# CAN-Transceiver.net
KiCad netlist of a schematic drawn in Altium Designer
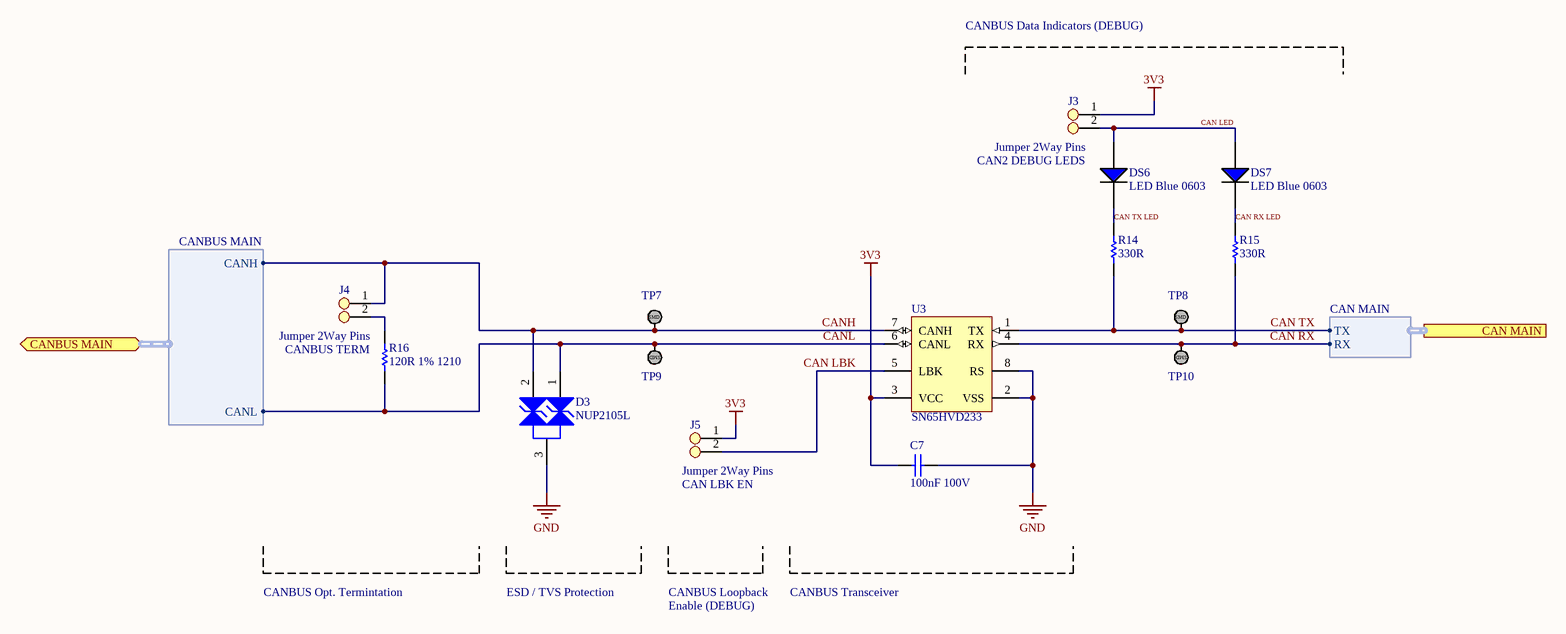
[diagram p0: CAN-Transceiver.SchDoc]

(export (version "E")
  (design (tool "Eeschema 10.0.6"))
  (components
    (comp (ref "C7")
      (value "100nF 100V")
      (footprint "Cap_Ceramic_0603")
      (description "Capacitor, Ceramic, SMD, 100nF, 100V, 5%, X7R, 0603")
      (libsource (lib "StandardCapacitors") (part "100nF 100V 5% X7R 0603"))
    )
    (comp (ref "D3")
      (value "NUP2105L")
      (footprint "NUP2105L")
      (libsource (lib "QUTMS_CANLibrary") (part "NUP2105L"))
    )
    (comp (ref "DS6")
      (value "LED Blue 0603")
      (footprint "LED BLUE 0603")
      (libsource (lib "QUTMS_LEDLibrary") (part "LED BLUE 0603"))
    )
    (comp (ref "DS7")
      (value "LED Blue 0603")
      (footprint "LED BLUE 0603")
      (libsource (lib "QUTMS_LEDLibrary") (part "LED BLUE 0603"))
    )
    (comp (ref "J3")
      (value "Jumper 2Way Pins")
      (footprint "Jumper_2Way_Pin")
      (description "Jumper 2Way Side Pins")
      (libsource (lib "QUTMS_JumperLibrary") (part "Jumper 2Way Side Pins"))
    )
    (comp (ref "J4")
      (value "Jumper 2Way Pins")
      (footprint "Jumper_2Way_Pin")
      (description "Jumper 2Way Side Pins")
      (libsource (lib "QUTMS_JumperLibrary") (part "Jumper 2Way Side Pins"))
    )
    (comp (ref "J5")
      (value "Jumper 2Way Pins")
      (footprint "Jumper_2Way_Pin")
      (description "Jumper 2Way Side Pins")
      (libsource (lib "QUTMS_JumperLibrary") (part "Jumper 2Way Side Pins"))
    )
    (comp (ref "R14")
      (value "330R")
      (footprint "Res_ThinFilm_0603")
      (description "Resistor, SMD, 330R, 0.1W, 5%, 0603")
      (libsource (lib "StandardResistors") (part "330R 5% 0603"))
    )
    (comp (ref "R15")
      (value "330R")
      (footprint "Res_ThinFilm_0603")
      (description "Resistor, SMD, 330R, 0.1W, 5%, 0603")
      (libsource (lib "StandardResistors") (part "330R 5% 0603"))
    )
    (comp (ref "R16")
      (value "120R 1% 1210")
      (footprint "Res_ThinFilm_1210")
      (description "Resistor, SMD, 120R, 0.25W, 1%, 1210")
      (libsource (lib "StandardResistors") (part "120R 1% 1210"))
    )
    (comp (ref "TP7")
      (value "TestPoint_SMD")
      (footprint "TestPointSMD")
      (libsource (lib "StandardTest") (part "TestPoint_SMD"))
    )
    (comp (ref "TP8")
      (value "TestPoint_SMD")
      (footprint "TestPointSMD")
      (libsource (lib "StandardTest") (part "TestPoint_SMD"))
    )
    (comp (ref "TP9")
      (value "TestPoint_SMD")
      (footprint "TestPointSMD")
      (libsource (lib "StandardTest") (part "TestPoint_SMD"))
    )
    (comp (ref "TP10")
      (value "TestPoint_SMD")
      (footprint "TestPointSMD")
      (libsource (lib "StandardTest") (part "TestPoint_SMD"))
    )
    (comp (ref "U3")
      (value "SN65HVD233")
      (footprint "SN65HVD233DR")
      (libsource (lib "QUTMS_CANLibrary") (part "SN65HVD233"))
    )
  )
  (nets
    (net (code "4") (name "/CAN LBK") (class "Default")
      (node (ref "J5") (pin "2") (pinfunction "2_2") (pintype "passive"))
      (node (ref "U3") (pin "5") (pinfunction "LBK_5") (pintype "passive"))
    )
    (net (code "5") (name "/CAN LED") (class "Default")
      (node (ref "DS6") (pin "1") (pinfunction "A_1") (pintype "passive"))
      (node (ref "DS7") (pin "1") (pinfunction "A_1") (pintype "passive"))
      (node (ref "J3") (pin "2") (pinfunction "2_2") (pintype "passive"))
    )
    (net (code "6") (name "/CAN RX") (class "Default")
      (node (ref "R15") (pin "1") (pinfunction "1_1") (pintype "passive"))
      (node (ref "TP10") (pin "1") (pinfunction "1_1") (pintype "passive"))
      (node (ref "U3") (pin "4") (pinfunction "RX_4") (pintype "output"))
    )
    (net (code "7") (name "/CAN RX LED") (class "Default")
      (node (ref "DS7") (pin "2") (pinfunction "C_2") (pintype "passive"))
      (node (ref "R15") (pin "2") (pinfunction "2_2") (pintype "passive"))
    )
    (net (code "8") (name "/CAN TX") (class "Default")
      (node (ref "R14") (pin "1") (pinfunction "1_1") (pintype "passive"))
      (node (ref "TP8") (pin "1") (pinfunction "1_1") (pintype "passive"))
      (node (ref "U3") (pin "1") (pinfunction "TX_1") (pintype "input"))
    )
    (net (code "9") (name "/CAN TX LED") (class "Default")
      (node (ref "DS6") (pin "2") (pinfunction "C_2") (pintype "passive"))
      (node (ref "R14") (pin "2") (pinfunction "2_2") (pintype "passive"))
    )
    (net (code "10") (name "/CANH") (class "Default")
      (node (ref "D3") (pin "2") (pinfunction "2_2") (pintype "passive"))
      (node (ref "J4") (pin "1") (pinfunction "1_1") (pintype "passive"))
      (node (ref "TP7") (pin "1") (pinfunction "1_1") (pintype "passive"))
      (node (ref "U3") (pin "7") (pinfunction "CANH_7") (pintype "bidirectional"))
    )
    (net (code "11") (name "/CANL") (class "Default")
      (node (ref "D3") (pin "1") (pinfunction "1_1") (pintype "passive"))
      (node (ref "R16") (pin "1") (pinfunction "1_1") (pintype "passive"))
      (node (ref "TP9") (pin "1") (pinfunction "1_1") (pintype "passive"))
      (node (ref "U3") (pin "6") (pinfunction "CANL_6") (pintype "bidirectional"))
    )
    (net (code "14") (name "3V3") (class "Default")
      (node (ref "C7") (pin "2") (pinfunction "2_2") (pintype "passive"))
      (node (ref "J3") (pin "1") (pinfunction "1_1") (pintype "passive"))
      (node (ref "J5") (pin "1") (pinfunction "1_1") (pintype "passive"))
      (node (ref "U3") (pin "3") (pinfunction "VCC_3") (pintype "passive"))
    )
    (net (code "15") (name "GND") (class "Default")
      (node (ref "C7") (pin "1") (pinfunction "1_1") (pintype "passive"))
      (node (ref "D3") (pin "3") (pinfunction "3_3") (pintype "passive"))
      (node (ref "U3") (pin "2") (pinfunction "VSS_2") (pintype "passive"))
      (node (ref "U3") (pin "8") (pinfunction "RS_8") (pintype "passive"))
    )
    (net (code "16") (name "Net-(J4-Pad2)") (class "Default")
      (node (ref "J4") (pin "2") (pinfunction "2_2") (pintype "passive"))
      (node (ref "R16") (pin "2") (pinfunction "2_2") (pintype "passive"))
    )
  )
)
